# Apo_Board_2017_PB.net
KiCad netlist of a schematic drawn in EAGLE
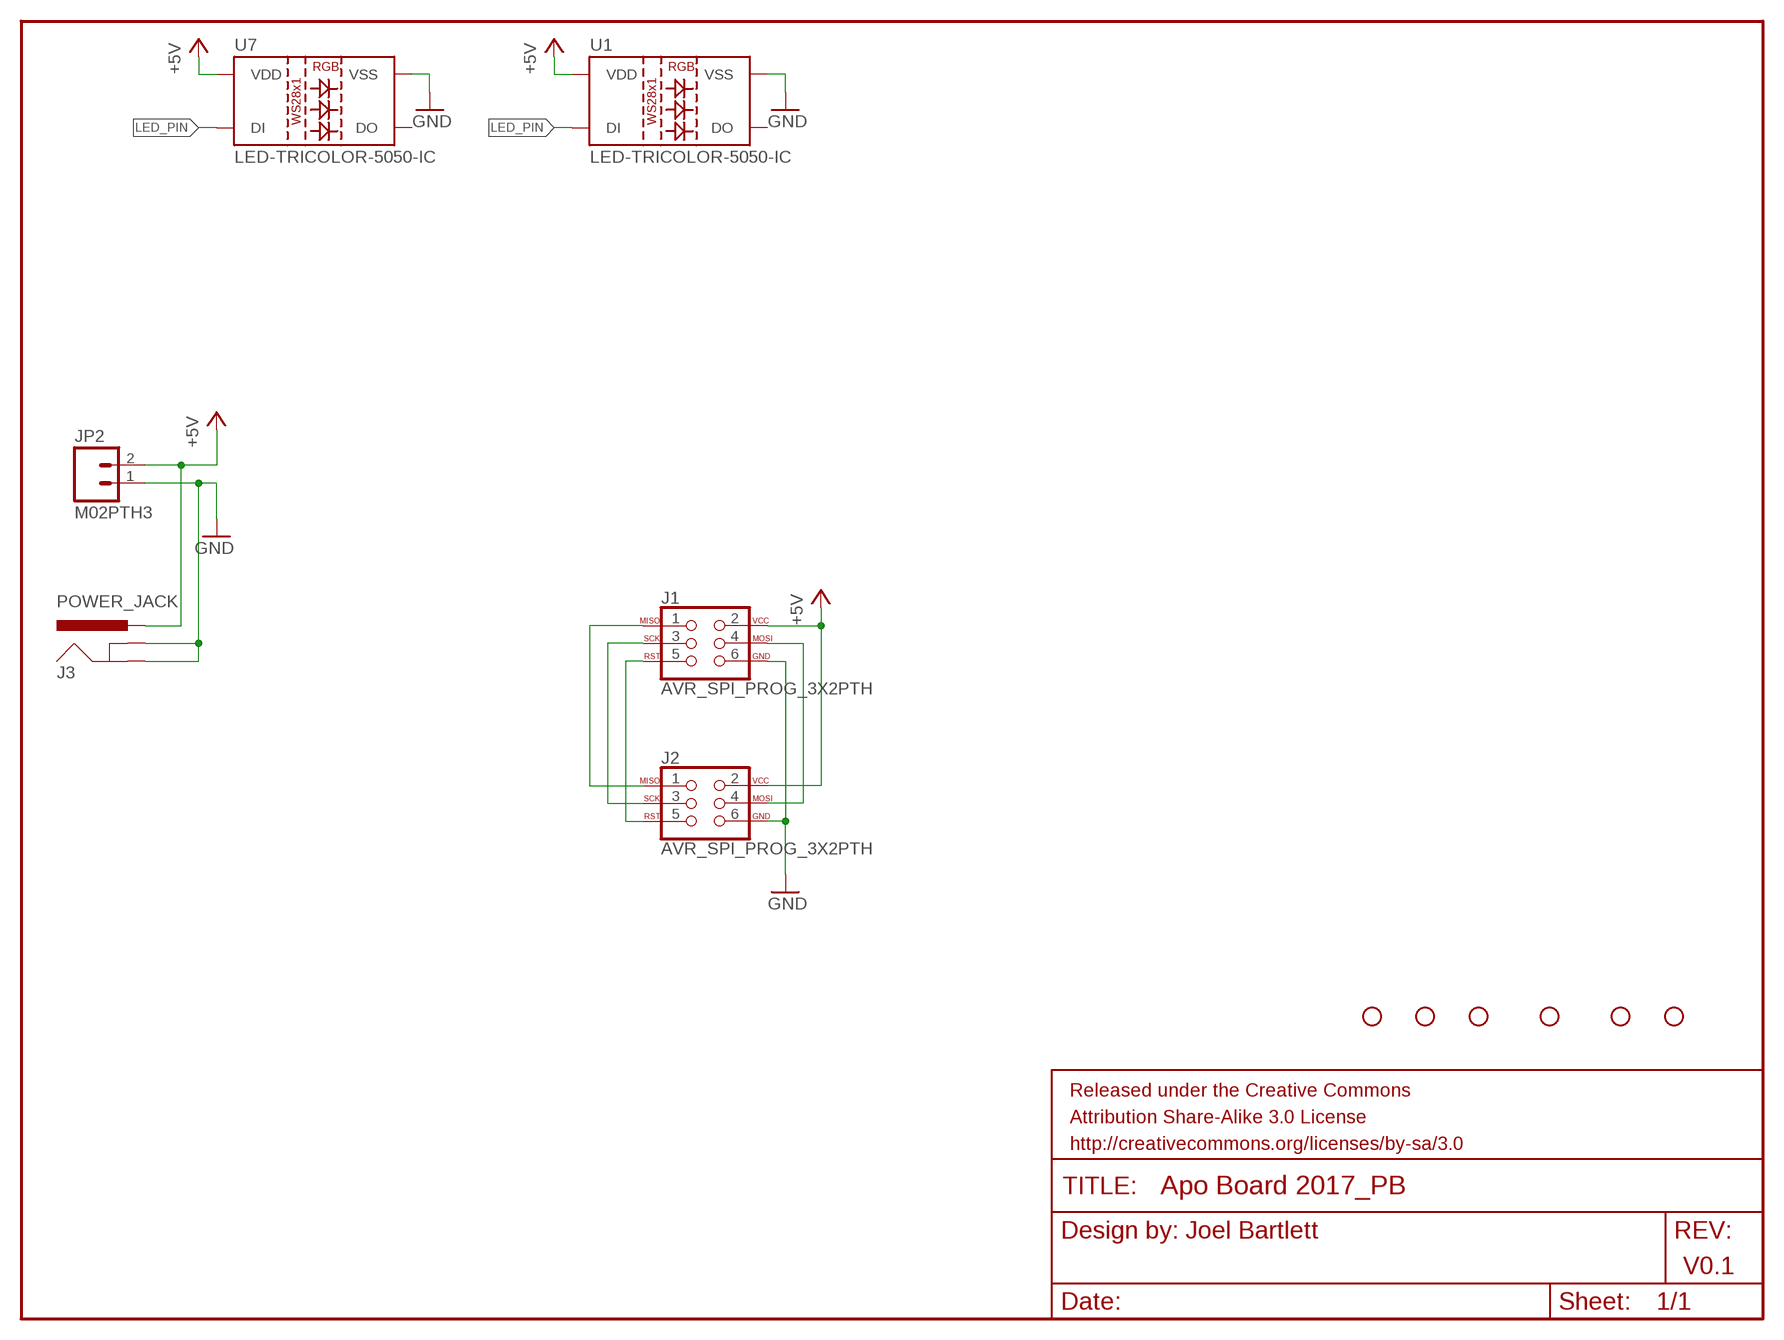
[diagram p0: schematic, sheet 1]

(export (version "E")
  (design (tool "Eeschema 10.0.6"))
  (components
    (comp (ref "FRAME1")
      (value "FRAME-LETTER")
      (footprint "eagle-import:CREATIVE_COMMONS")
      (libsource (lib "eagle-import") (part "FRAME-LETTER"))
    )
    (comp (ref "H1")
      (value "STAND-OFF")
      (footprint "eagle-import:STAND-OFF")
      (libsource (lib "eagle-import") (part "STAND-OFF"))
    )
    (comp (ref "H2")
      (value "STAND-OFF")
      (footprint "eagle-import:STAND-OFF")
      (libsource (lib "eagle-import") (part "STAND-OFF"))
    )
    (comp (ref "H3")
      (value "STAND-OFF")
      (footprint "eagle-import:STAND-OFF")
      (libsource (lib "eagle-import") (part "STAND-OFF"))
    )
    (comp (ref "H4")
      (value "STAND-OFF")
      (footprint "eagle-import:STAND-OFF")
      (libsource (lib "eagle-import") (part "STAND-OFF"))
    )
    (comp (ref "H5")
      (value "STAND-OFF")
      (footprint "eagle-import:STAND-OFF")
      (libsource (lib "eagle-import") (part "STAND-OFF"))
    )
    (comp (ref "H6")
      (value "STAND-OFF")
      (footprint "eagle-import:STAND-OFF")
      (libsource (lib "eagle-import") (part "STAND-OFF"))
    )
    (comp (ref "J1")
      (value "AVR_SPI_PROG_3X2PTH")
      (footprint "eagle-import:2X3")
      (libsource (lib "eagle-import") (part "AVR_SPI_PROG_3X2PTH"))
    )
    (comp (ref "J2")
      (value "AVR_SPI_PROG_3X2PTH")
      (footprint "eagle-import:2X3")
      (libsource (lib "eagle-import") (part "AVR_SPI_PROG_3X2PTH"))
    )
    (comp (ref "J3")
      (value "POWER_JACK")
      (footprint "eagle-import:POWER_JACK_PTH")
      (libsource (lib "eagle-import") (part "POWER_JACK"))
    )
    (comp (ref "JP2")
      (value "M02PTH3")
      (footprint "eagle-import:1X02_LONGPADS")
      (libsource (lib "eagle-import") (part "M02PTH3"))
    )
    (comp (ref "U1")
      (value "LED-TRICOLOR-5050-IC")
      (footprint "eagle-import:LED-RGB-THRU")
      (libsource (lib "eagle-import") (part "LED-TRICOLOR-5050-IC"))
    )
    (comp (ref "U7")
      (value "LED-TRICOLOR-5050-IC")
      (footprint "eagle-import:LED-RGB-THRU")
      (libsource (lib "eagle-import") (part "LED-TRICOLOR-5050-IC"))
    )
  )
  (nets
    (net (code "1") (name "+5V") (class "Default")
      (node (ref "J1") (pin "2") (pinfunction "2_2") (pintype "passive"))
      (node (ref "J2") (pin "2") (pinfunction "2_2") (pintype "passive"))
      (node (ref "J3") (pin "PWR") (pinfunction "PWR_PWR") (pintype "bidirectional"))
      (node (ref "JP2") (pin "2") (pinfunction "2_2") (pintype "passive"))
      (node (ref "U1") (pin "2") (pinfunction "VDD_2") (pintype "bidirectional"))
      (node (ref "U7") (pin "2") (pinfunction "VDD_2") (pintype "bidirectional"))
    )
    (net (code "2") (name "GND") (class "Default")
      (node (ref "J1") (pin "6") (pinfunction "6_6") (pintype "passive"))
      (node (ref "J2") (pin "6") (pinfunction "6_6") (pintype "passive"))
      (node (ref "J3") (pin "GND") (pinfunction "GND_GND") (pintype "bidirectional"))
      (node (ref "J3") (pin "GNDBREAK") (pinfunction "GNDBREAK_GNDBREAK") (pintype "bidirectional"))
      (node (ref "JP2") (pin "1") (pinfunction "1_1") (pintype "passive"))
      (node (ref "U1") (pin "3") (pinfunction "VSS_3") (pintype "bidirectional"))
      (node (ref "U7") (pin "3") (pinfunction "VSS_3") (pintype "bidirectional"))
    )
    (net (code "3") (name "LED_PIN") (class "Default")
      (node (ref "U1") (pin "1") (pinfunction "DI_1") (pintype "bidirectional"))
      (node (ref "U7") (pin "1") (pinfunction "DI_1") (pintype "bidirectional"))
    )
    (net (code "4") (name "Net-(J1-Pad1)") (class "Default")
      (node (ref "J1") (pin "1") (pinfunction "1_1") (pintype "passive"))
      (node (ref "J2") (pin "1") (pinfunction "1_1") (pintype "passive"))
    )
    (net (code "5") (name "Net-(J1-Pad3)") (class "Default")
      (node (ref "J1") (pin "3") (pinfunction "3_3") (pintype "passive"))
      (node (ref "J2") (pin "3") (pinfunction "3_3") (pintype "passive"))
    )
    (net (code "6") (name "Net-(J1-Pad4)") (class "Default")
      (node (ref "J1") (pin "4") (pinfunction "4_4") (pintype "passive"))
      (node (ref "J2") (pin "4") (pinfunction "4_4") (pintype "passive"))
    )
    (net (code "7") (name "Net-(J1-Pad5)") (class "Default")
      (node (ref "J1") (pin "5") (pinfunction "5_5") (pintype "passive"))
      (node (ref "J2") (pin "5") (pinfunction "5_5") (pintype "passive"))
    )
    (net (code "8") (name "unconnected-(U1-DO-Pad4)") (class "Default")
      (node (ref "U1") (pin "4") (pinfunction "DO_4") (pintype "bidirectional"))
    )
    (net (code "9") (name "unconnected-(U7-DO-Pad4)") (class "Default")
      (node (ref "U7") (pin "4") (pinfunction "DO_4") (pintype "bidirectional"))
    )
  )
)
